# S7CAS-PLEIADES-CARTE-MERE_P07_FPGA_4-5.net
KiCad netlist of a schematic drawn in Altium Designer
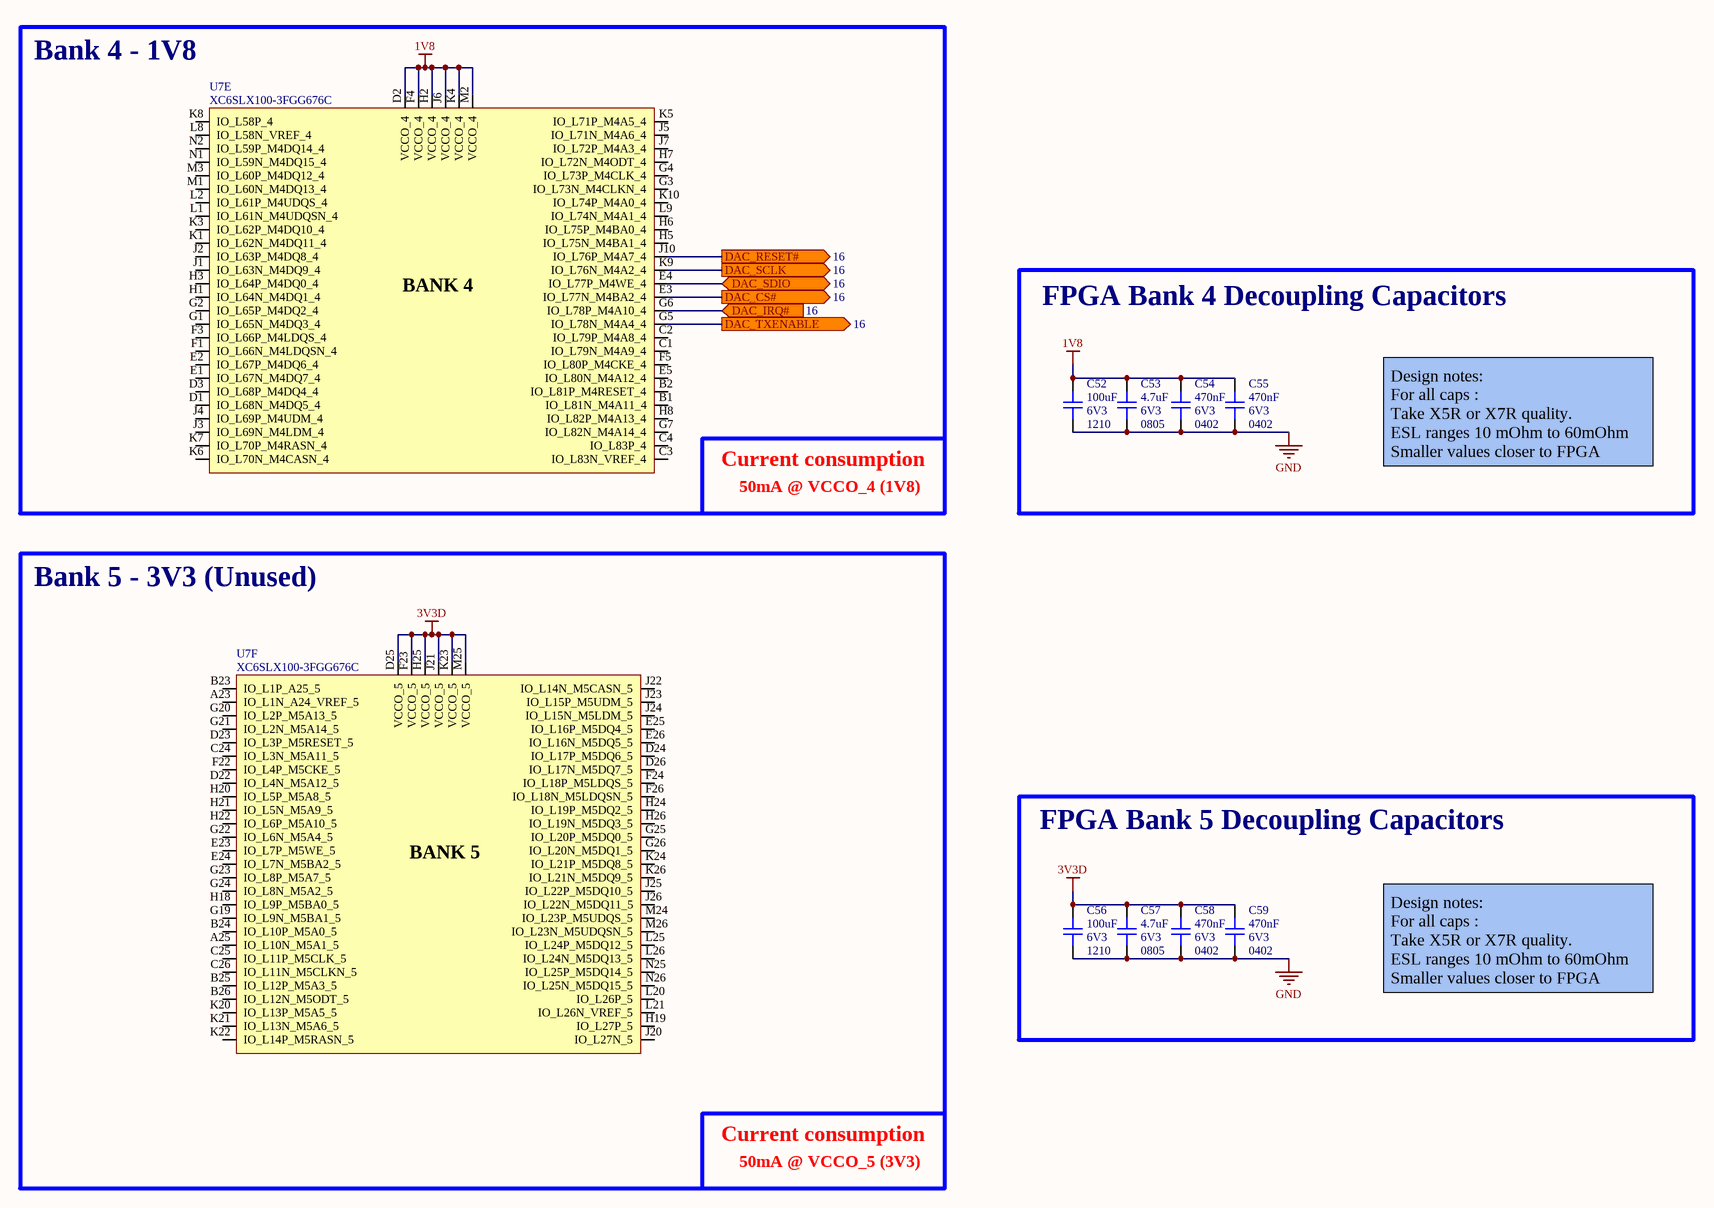
[diagram p0: S7CAS-PLEIADES-CARTE-MERE_P07_FPGA_4-5.SchDoc]

(export (version "E")
  (design (tool "Eeschema 10.0.6"))
  (components
    (comp (ref "C52")
      (value "100uF")
      (footprint "CAP_1210")
      (description "CAP - 1210")
      (fields
        (field (name "VOLTAGE") "6V3")
        (field (name "PACKAGE") "1210")
        (field (name "CREATEDBY") "Jonathan Bouchard")
      )
      (libsource (lib "S7CAS_LIB2021") (part "CAP - 1210"))
    )
    (comp (ref "C53")
      (value "4.7uF")
      (footprint "CAP_0805")
      (description "CAP - 0805")
      (fields
        (field (name "VOLTAGE") "6V3")
        (field (name "PACKAGE") "0805")
        (field (name "CREATEDBY") "Jonathan Bouchard")
      )
      (libsource (lib "S7CAS_LIB2021") (part "CAP - 0805"))
    )
    (comp (ref "C54")
      (value "470nF")
      (footprint "CAP_0402")
      (description "CAP - 0402")
      (fields
        (field (name "VOLTAGE") "6V3")
        (field (name "PACKAGE") "0402")
        (field (name "CREATEDBY") "Jonathan Bouchard")
      )
      (libsource (lib "S7CAS_LIB2021") (part "CAP - 0402"))
    )
    (comp (ref "C55")
      (value "470nF")
      (footprint "CAP_0402")
      (description "CAP - 0402")
      (fields
        (field (name "VOLTAGE") "6V3")
        (field (name "PACKAGE") "0402")
        (field (name "CREATEDBY") "Jonathan Bouchard")
      )
      (libsource (lib "S7CAS_LIB2021") (part "CAP - 0402"))
    )
    (comp (ref "C56")
      (value "100uF")
      (footprint "CAP_1210")
      (description "CAP - 1210")
      (fields
        (field (name "VOLTAGE") "6V3")
        (field (name "PACKAGE") "1210")
        (field (name "CREATEDBY") "Jonathan Bouchard")
      )
      (libsource (lib "S7CAS_LIB2021") (part "CAP - 1210"))
    )
    (comp (ref "C57")
      (value "4.7uF")
      (footprint "CAP_0805")
      (description "CAP - 0805")
      (fields
        (field (name "VOLTAGE") "6V3")
        (field (name "PACKAGE") "0805")
        (field (name "CREATEDBY") "Jonathan Bouchard")
      )
      (libsource (lib "S7CAS_LIB2021") (part "CAP - 0805"))
    )
    (comp (ref "C58")
      (value "470nF")
      (footprint "CAP_0402")
      (description "CAP - 0402")
      (fields
        (field (name "VOLTAGE") "6V3")
        (field (name "PACKAGE") "0402")
        (field (name "CREATEDBY") "Jonathan Bouchard")
      )
      (libsource (lib "S7CAS_LIB2021") (part "CAP - 0402"))
    )
    (comp (ref "C59")
      (value "470nF")
      (footprint "CAP_0402")
      (description "CAP - 0402")
      (fields
        (field (name "VOLTAGE") "6V3")
        (field (name "PACKAGE") "0402")
        (field (name "CREATEDBY") "Jonathan Bouchard")
      )
      (libsource (lib "S7CAS_LIB2021") (part "CAP - 0402"))
    )
    (comp (ref "U7")
      (value "XC6SLX100-3FGG676C")
      (footprint "FPGA_XILINX_FGG676")
      (description "FPGA - XILINX SPARTAN 6 480 I/O - BGA-676")
      (fields
        (field (name "VOLTAGE") "1.14 V ~ 1.26 V")
        (field (name "MFG") "Xilinx")
        (field (name "CREATEDBY") "Jonathan Bouchard")
      )
      (libsource (lib "S7CAS_LIB2021") (part "FPGA_XC6SLX100-3FGG676C"))
    )
  )
  (nets
    (net (code "1") (name "/DAC_CS#") (class "Default")
      (node (ref "U7") (pin "E3") (pinfunction "IO_L77N_M4BA2_4_E3") (pintype "passive"))
    )
    (net (code "2") (name "/DAC_IRQ#") (class "Default")
      (node (ref "U7") (pin "G6") (pinfunction "IO_L78P_M4A10_4_G6") (pintype "passive"))
    )
    (net (code "3") (name "/DAC_RESET#") (class "Default")
      (node (ref "U7") (pin "J10") (pinfunction "IO_L76P_M4A7_4_J10") (pintype "passive"))
    )
    (net (code "4") (name "/DAC_SCLK") (class "Default")
      (node (ref "U7") (pin "K9") (pinfunction "IO_L76N_M4A2_4_K9") (pintype "passive"))
    )
    (net (code "5") (name "/DAC_SDIO") (class "Default")
      (node (ref "U7") (pin "E4") (pinfunction "IO_L77P_M4WE_4_E4") (pintype "passive"))
    )
    (net (code "6") (name "/DAC_TXENABLE") (class "Default")
      (node (ref "U7") (pin "G5") (pinfunction "IO_L78N_M4A4_4_G5") (pintype "passive"))
    )
    (net (code "7") (name "1V8") (class "Default")
      (node (ref "C52") (pin "2") (pinfunction "2_2") (pintype "passive"))
      (node (ref "C53") (pin "2") (pinfunction "2_2") (pintype "passive"))
      (node (ref "C54") (pin "2") (pinfunction "2_2") (pintype "passive"))
      (node (ref "C55") (pin "2") (pinfunction "2_2") (pintype "passive"))
      (node (ref "U7") (pin "D2") (pinfunction "VCCO_4_D2") (pintype "passive"))
      (node (ref "U7") (pin "F4") (pinfunction "VCCO_4_F4") (pintype "passive"))
      (node (ref "U7") (pin "H2") (pinfunction "VCCO_4_H2") (pintype "passive"))
      (node (ref "U7") (pin "J6") (pinfunction "VCCO_4_J6") (pintype "passive"))
      (node (ref "U7") (pin "K4") (pinfunction "VCCO_4_K4") (pintype "passive"))
      (node (ref "U7") (pin "M2") (pinfunction "VCCO_4_M2") (pintype "passive"))
    )
    (net (code "8") (name "3V3D") (class "Default")
      (node (ref "C56") (pin "2") (pinfunction "2_2") (pintype "passive"))
      (node (ref "C57") (pin "2") (pinfunction "2_2") (pintype "passive"))
      (node (ref "C58") (pin "2") (pinfunction "2_2") (pintype "passive"))
      (node (ref "C59") (pin "2") (pinfunction "2_2") (pintype "passive"))
      (node (ref "U7") (pin "D25") (pinfunction "VCCO_5_D25") (pintype "passive"))
      (node (ref "U7") (pin "F23") (pinfunction "VCCO_5_F23") (pintype "passive"))
      (node (ref "U7") (pin "H25") (pinfunction "VCCO_5_H25") (pintype "passive"))
      (node (ref "U7") (pin "J21") (pinfunction "VCCO_5_J21") (pintype "passive"))
      (node (ref "U7") (pin "K23") (pinfunction "VCCO_5_K23") (pintype "passive"))
      (node (ref "U7") (pin "M25") (pinfunction "VCCO_5_M25") (pintype "passive"))
    )
    (net (code "9") (name "GND") (class "Default")
      (node (ref "C52") (pin "1") (pinfunction "1_1") (pintype "passive"))
      (node (ref "C53") (pin "1") (pinfunction "1_1") (pintype "passive"))
      (node (ref "C54") (pin "1") (pinfunction "1_1") (pintype "passive"))
      (node (ref "C55") (pin "1") (pinfunction "1_1") (pintype "passive"))
      (node (ref "C56") (pin "1") (pinfunction "1_1") (pintype "passive"))
      (node (ref "C57") (pin "1") (pinfunction "1_1") (pintype "passive"))
      (node (ref "C58") (pin "1") (pinfunction "1_1") (pintype "passive"))
      (node (ref "C59") (pin "1") (pinfunction "1_1") (pintype "passive"))
    )
    (net (code "10") (name "unconnected-(U7E-IO_L58N_VREF_4-PadL8)") (class "Default")
      (node (ref "U7") (pin "L8") (pinfunction "IO_L58N_VREF_4_L8") (pintype "passive"))
    )
    (net (code "11") (name "unconnected-(U7E-IO_L58P_4-PadK8)") (class "Default")
      (node (ref "U7") (pin "K8") (pinfunction "IO_L58P_4_K8") (pintype "passive"))
    )
    (net (code "12") (name "unconnected-(U7E-IO_L59N_M4DQ15_4-PadN1)") (class "Default")
      (node (ref "U7") (pin "N1") (pinfunction "IO_L59N_M4DQ15_4_N1") (pintype "passive"))
    )
    (net (code "13") (name "unconnected-(U7E-IO_L59P_M4DQ14_4-PadN2)") (class "Default")
      (node (ref "U7") (pin "N2") (pinfunction "IO_L59P_M4DQ14_4_N2") (pintype "passive"))
    )
    (net (code "14") (name "unconnected-(U7E-IO_L60N_M4DQ13_4-PadM1)") (class "Default")
      (node (ref "U7") (pin "M1") (pinfunction "IO_L60N_M4DQ13_4_M1") (pintype "passive"))
    )
    (net (code "15") (name "unconnected-(U7E-IO_L60P_M4DQ12_4-PadM3)") (class "Default")
      (node (ref "U7") (pin "M3") (pinfunction "IO_L60P_M4DQ12_4_M3") (pintype "passive"))
    )
    (net (code "16") (name "unconnected-(U7E-IO_L61N_M4UDQSN_4-PadL1)") (class "Default")
      (node (ref "U7") (pin "L1") (pinfunction "IO_L61N_M4UDQSN_4_L1") (pintype "passive"))
    )
    (net (code "17") (name "unconnected-(U7E-IO_L61P_M4UDQS_4-PadL2)") (class "Default")
      (node (ref "U7") (pin "L2") (pinfunction "IO_L61P_M4UDQS_4_L2") (pintype "passive"))
    )
    (net (code "18") (name "unconnected-(U7E-IO_L62N_M4DQ11_4-PadK1)") (class "Default")
      (node (ref "U7") (pin "K1") (pinfunction "IO_L62N_M4DQ11_4_K1") (pintype "passive"))
    )
    (net (code "19") (name "unconnected-(U7E-IO_L62P_M4DQ10_4-PadK3)") (class "Default")
      (node (ref "U7") (pin "K3") (pinfunction "IO_L62P_M4DQ10_4_K3") (pintype "passive"))
    )
    (net (code "20") (name "unconnected-(U7E-IO_L63N_M4DQ9_4-PadJ1)") (class "Default")
      (node (ref "U7") (pin "J1") (pinfunction "IO_L63N_M4DQ9_4_J1") (pintype "passive"))
    )
    (net (code "21") (name "unconnected-(U7E-IO_L63P_M4DQ8_4-PadJ2)") (class "Default")
      (node (ref "U7") (pin "J2") (pinfunction "IO_L63P_M4DQ8_4_J2") (pintype "passive"))
    )
    (net (code "22") (name "unconnected-(U7E-IO_L64N_M4DQ1_4-PadH1)") (class "Default")
      (node (ref "U7") (pin "H1") (pinfunction "IO_L64N_M4DQ1_4_H1") (pintype "passive"))
    )
    (net (code "23") (name "unconnected-(U7E-IO_L64P_M4DQ0_4-PadH3)") (class "Default")
      (node (ref "U7") (pin "H3") (pinfunction "IO_L64P_M4DQ0_4_H3") (pintype "passive"))
    )
    (net (code "24") (name "unconnected-(U7E-IO_L65N_M4DQ3_4-PadG1)") (class "Default")
      (node (ref "U7") (pin "G1") (pinfunction "IO_L65N_M4DQ3_4_G1") (pintype "passive"))
    )
    (net (code "25") (name "unconnected-(U7E-IO_L65P_M4DQ2_4-PadG2)") (class "Default")
      (node (ref "U7") (pin "G2") (pinfunction "IO_L65P_M4DQ2_4_G2") (pintype "passive"))
    )
    (net (code "26") (name "unconnected-(U7E-IO_L66N_M4LDQSN_4-PadF1)") (class "Default")
      (node (ref "U7") (pin "F1") (pinfunction "IO_L66N_M4LDQSN_4_F1") (pintype "passive"))
    )
    (net (code "27") (name "unconnected-(U7E-IO_L66P_M4LDQS_4-PadF3)") (class "Default")
      (node (ref "U7") (pin "F3") (pinfunction "IO_L66P_M4LDQS_4_F3") (pintype "passive"))
    )
    (net (code "28") (name "unconnected-(U7E-IO_L67N_M4DQ7_4-PadE1)") (class "Default")
      (node (ref "U7") (pin "E1") (pinfunction "IO_L67N_M4DQ7_4_E1") (pintype "passive"))
    )
    (net (code "29") (name "unconnected-(U7E-IO_L67P_M4DQ6_4-PadE2)") (class "Default")
      (node (ref "U7") (pin "E2") (pinfunction "IO_L67P_M4DQ6_4_E2") (pintype "passive"))
    )
    (net (code "30") (name "unconnected-(U7E-IO_L68N_M4DQ5_4-PadD1)") (class "Default")
      (node (ref "U7") (pin "D1") (pinfunction "IO_L68N_M4DQ5_4_D1") (pintype "passive"))
    )
    (net (code "31") (name "unconnected-(U7E-IO_L68P_M4DQ4_4-PadD3)") (class "Default")
      (node (ref "U7") (pin "D3") (pinfunction "IO_L68P_M4DQ4_4_D3") (pintype "passive"))
    )
    (net (code "32") (name "unconnected-(U7E-IO_L69N_M4LDM_4-PadJ3)") (class "Default")
      (node (ref "U7") (pin "J3") (pinfunction "IO_L69N_M4LDM_4_J3") (pintype "passive"))
    )
    (net (code "33") (name "unconnected-(U7E-IO_L69P_M4UDM_4-PadJ4)") (class "Default")
      (node (ref "U7") (pin "J4") (pinfunction "IO_L69P_M4UDM_4_J4") (pintype "passive"))
    )
    (net (code "34") (name "unconnected-(U7E-IO_L70N_M4CASN_4-PadK6)") (class "Default")
      (node (ref "U7") (pin "K6") (pinfunction "IO_L70N_M4CASN_4_K6") (pintype "passive"))
    )
    (net (code "35") (name "unconnected-(U7E-IO_L70P_M4RASN_4-PadK7)") (class "Default")
      (node (ref "U7") (pin "K7") (pinfunction "IO_L70P_M4RASN_4_K7") (pintype "passive"))
    )
    (net (code "36") (name "unconnected-(U7E-IO_L71N_M4A6_4-PadJ5)") (class "Default")
      (node (ref "U7") (pin "J5") (pinfunction "IO_L71N_M4A6_4_J5") (pintype "passive"))
    )
    (net (code "37") (name "unconnected-(U7E-IO_L71P_M4A5_4-PadK5)") (class "Default")
      (node (ref "U7") (pin "K5") (pinfunction "IO_L71P_M4A5_4_K5") (pintype "passive"))
    )
    (net (code "38") (name "unconnected-(U7E-IO_L72N_M4ODT_4-PadH7)") (class "Default")
      (node (ref "U7") (pin "H7") (pinfunction "IO_L72N_M4ODT_4_H7") (pintype "passive"))
    )
    (net (code "39") (name "unconnected-(U7E-IO_L72P_M4A3_4-PadJ7)") (class "Default")
      (node (ref "U7") (pin "J7") (pinfunction "IO_L72P_M4A3_4_J7") (pintype "passive"))
    )
    (net (code "40") (name "unconnected-(U7E-IO_L73N_M4CLKN_4-PadG3)") (class "Default")
      (node (ref "U7") (pin "G3") (pinfunction "IO_L73N_M4CLKN_4_G3") (pintype "passive"))
    )
    (net (code "41") (name "unconnected-(U7E-IO_L73P_M4CLK_4-PadG4)") (class "Default")
      (node (ref "U7") (pin "G4") (pinfunction "IO_L73P_M4CLK_4_G4") (pintype "passive"))
    )
    (net (code "42") (name "unconnected-(U7E-IO_L74N_M4A1_4-PadL9)") (class "Default")
      (node (ref "U7") (pin "L9") (pinfunction "IO_L74N_M4A1_4_L9") (pintype "passive"))
    )
    (net (code "43") (name "unconnected-(U7E-IO_L74P_M4A0_4-PadK10)") (class "Default")
      (node (ref "U7") (pin "K10") (pinfunction "IO_L74P_M4A0_4_K10") (pintype "passive"))
    )
    (net (code "44") (name "unconnected-(U7E-IO_L75N_M4BA1_4-PadH5)") (class "Default")
      (node (ref "U7") (pin "H5") (pinfunction "IO_L75N_M4BA1_4_H5") (pintype "passive"))
    )
    (net (code "45") (name "unconnected-(U7E-IO_L75P_M4BA0_4-PadH6)") (class "Default")
      (node (ref "U7") (pin "H6") (pinfunction "IO_L75P_M4BA0_4_H6") (pintype "passive"))
    )
    (net (code "46") (name "unconnected-(U7E-IO_L79N_M4A9_4-PadC1)") (class "Default")
      (node (ref "U7") (pin "C1") (pinfunction "IO_L79N_M4A9_4_C1") (pintype "passive"))
    )
    (net (code "47") (name "unconnected-(U7E-IO_L79P_M4A8_4-PadC2)") (class "Default")
      (node (ref "U7") (pin "C2") (pinfunction "IO_L79P_M4A8_4_C2") (pintype "passive"))
    )
    (net (code "48") (name "unconnected-(U7E-IO_L80N_M4A12_4-PadE5)") (class "Default")
      (node (ref "U7") (pin "E5") (pinfunction "IO_L80N_M4A12_4_E5") (pintype "passive"))
    )
    (net (code "49") (name "unconnected-(U7E-IO_L80P_M4CKE_4-PadF5)") (class "Default")
      (node (ref "U7") (pin "F5") (pinfunction "IO_L80P_M4CKE_4_F5") (pintype "passive"))
    )
    (net (code "50") (name "unconnected-(U7E-IO_L81N_M4A11_4-PadB1)") (class "Default")
      (node (ref "U7") (pin "B1") (pinfunction "IO_L81N_M4A11_4_B1") (pintype "passive"))
    )
    (net (code "51") (name "unconnected-(U7E-IO_L81P_M4RESET_4-PadB2)") (class "Default")
      (node (ref "U7") (pin "B2") (pinfunction "IO_L81P_M4RESET_4_B2") (pintype "passive"))
    )
    (net (code "52") (name "unconnected-(U7E-IO_L82N_M4A14_4-PadG7)") (class "Default")
      (node (ref "U7") (pin "G7") (pinfunction "IO_L82N_M4A14_4_G7") (pintype "passive"))
    )
    (net (code "53") (name "unconnected-(U7E-IO_L82P_M4A13_4-PadH8)") (class "Default")
      (node (ref "U7") (pin "H8") (pinfunction "IO_L82P_M4A13_4_H8") (pintype "passive"))
    )
    (net (code "54") (name "unconnected-(U7E-IO_L83N_VREF_4-PadC3)") (class "Default")
      (node (ref "U7") (pin "C3") (pinfunction "IO_L83N_VREF_4_C3") (pintype "passive"))
    )
    (net (code "55") (name "unconnected-(U7E-IO_L83P_4-PadC4)") (class "Default")
      (node (ref "U7") (pin "C4") (pinfunction "IO_L83P_4_C4") (pintype "passive"))
    )
    (net (code "56") (name "unconnected-(U7F-IO_L1N_A24_VREF_5-PadA23)") (class "Default")
      (node (ref "U7") (pin "A23") (pinfunction "IO_L1N_A24_VREF_5_A23") (pintype "passive"))
    )
    (net (code "57") (name "unconnected-(U7F-IO_L1P_A25_5-PadB23)") (class "Default")
      (node (ref "U7") (pin "B23") (pinfunction "IO_L1P_A25_5_B23") (pintype "passive"))
    )
    (net (code "58") (name "unconnected-(U7F-IO_L2N_M5A14_5-PadG21)") (class "Default")
      (node (ref "U7") (pin "G21") (pinfunction "IO_L2N_M5A14_5_G21") (pintype "passive"))
    )
    (net (code "59") (name "unconnected-(U7F-IO_L2P_M5A13_5-PadG20)") (class "Default")
      (node (ref "U7") (pin "G20") (pinfunction "IO_L2P_M5A13_5_G20") (pintype "passive"))
    )
    (net (code "60") (name "unconnected-(U7F-IO_L3N_M5A11_5-PadC24)") (class "Default")
      (node (ref "U7") (pin "C24") (pinfunction "IO_L3N_M5A11_5_C24") (pintype "passive"))
    )
    (net (code "61") (name "unconnected-(U7F-IO_L3P_M5RESET_5-PadD23)") (class "Default")
      (node (ref "U7") (pin "D23") (pinfunction "IO_L3P_M5RESET_5_D23") (pintype "passive"))
    )
    (net (code "62") (name "unconnected-(U7F-IO_L4N_M5A12_5-PadD22)") (class "Default")
      (node (ref "U7") (pin "D22") (pinfunction "IO_L4N_M5A12_5_D22") (pintype "passive"))
    )
    (net (code "63") (name "unconnected-(U7F-IO_L4P_M5CKE_5-PadF22)") (class "Default")
      (node (ref "U7") (pin "F22") (pinfunction "IO_L4P_M5CKE_5_F22") (pintype "passive"))
    )
    (net (code "64") (name "unconnected-(U7F-IO_L5N_M5A9_5-PadH21)") (class "Default")
      (node (ref "U7") (pin "H21") (pinfunction "IO_L5N_M5A9_5_H21") (pintype "passive"))
    )
    (net (code "65") (name "unconnected-(U7F-IO_L5P_M5A8_5-PadH20)") (class "Default")
      (node (ref "U7") (pin "H20") (pinfunction "IO_L5P_M5A8_5_H20") (pintype "passive"))
    )
    (net (code "66") (name "unconnected-(U7F-IO_L6N_M5A4_5-PadG22)") (class "Default")
      (node (ref "U7") (pin "G22") (pinfunction "IO_L6N_M5A4_5_G22") (pintype "passive"))
    )
    (net (code "67") (name "unconnected-(U7F-IO_L6P_M5A10_5-PadH22)") (class "Default")
      (node (ref "U7") (pin "H22") (pinfunction "IO_L6P_M5A10_5_H22") (pintype "passive"))
    )
    (net (code "68") (name "unconnected-(U7F-IO_L7N_M5BA2_5-PadE24)") (class "Default")
      (node (ref "U7") (pin "E24") (pinfunction "IO_L7N_M5BA2_5_E24") (pintype "passive"))
    )
    (net (code "69") (name "unconnected-(U7F-IO_L7P_M5WE_5-PadE23)") (class "Default")
      (node (ref "U7") (pin "E23") (pinfunction "IO_L7P_M5WE_5_E23") (pintype "passive"))
    )
    (net (code "70") (name "unconnected-(U7F-IO_L8N_M5A2_5-PadG24)") (class "Default")
      (node (ref "U7") (pin "G24") (pinfunction "IO_L8N_M5A2_5_G24") (pintype "passive"))
    )
    (net (code "71") (name "unconnected-(U7F-IO_L8P_M5A7_5-PadG23)") (class "Default")
      (node (ref "U7") (pin "G23") (pinfunction "IO_L8P_M5A7_5_G23") (pintype "passive"))
    )
    (net (code "72") (name "unconnected-(U7F-IO_L9N_M5BA1_5-PadG19)") (class "Default")
      (node (ref "U7") (pin "G19") (pinfunction "IO_L9N_M5BA1_5_G19") (pintype "passive"))
    )
    (net (code "73") (name "unconnected-(U7F-IO_L9P_M5BA0_5-PadH18)") (class "Default")
      (node (ref "U7") (pin "H18") (pinfunction "IO_L9P_M5BA0_5_H18") (pintype "passive"))
    )
    (net (code "74") (name "unconnected-(U7F-IO_L10N_M5A1_5-PadA25)") (class "Default")
      (node (ref "U7") (pin "A25") (pinfunction "IO_L10N_M5A1_5_A25") (pintype "passive"))
    )
    (net (code "75") (name "unconnected-(U7F-IO_L10P_M5A0_5-PadB24)") (class "Default")
      (node (ref "U7") (pin "B24") (pinfunction "IO_L10P_M5A0_5_B24") (pintype "passive"))
    )
    (net (code "76") (name "unconnected-(U7F-IO_L11N_M5CLKN_5-PadC26)") (class "Default")
      (node (ref "U7") (pin "C26") (pinfunction "IO_L11N_M5CLKN_5_C26") (pintype "passive"))
    )
    (net (code "77") (name "unconnected-(U7F-IO_L11P_M5CLK_5-PadC25)") (class "Default")
      (node (ref "U7") (pin "C25") (pinfunction "IO_L11P_M5CLK_5_C25") (pintype "passive"))
    )
    (net (code "78") (name "unconnected-(U7F-IO_L12N_M5ODT_5-PadB26)") (class "Default")
      (node (ref "U7") (pin "B26") (pinfunction "IO_L12N_M5ODT_5_B26") (pintype "passive"))
    )
    (net (code "79") (name "unconnected-(U7F-IO_L12P_M5A3_5-PadB25)") (class "Default")
      (node (ref "U7") (pin "B25") (pinfunction "IO_L12P_M5A3_5_B25") (pintype "passive"))
    )
    (net (code "80") (name "unconnected-(U7F-IO_L13N_M5A6_5-PadK21)") (class "Default")
      (node (ref "U7") (pin "K21") (pinfunction "IO_L13N_M5A6_5_K21") (pintype "passive"))
    )
    (net (code "81") (name "unconnected-(U7F-IO_L13P_M5A5_5-PadK20)") (class "Default")
      (node (ref "U7") (pin "K20") (pinfunction "IO_L13P_M5A5_5_K20") (pintype "passive"))
    )
    (net (code "82") (name "unconnected-(U7F-IO_L14N_M5CASN_5-PadJ22)") (class "Default")
      (node (ref "U7") (pin "J22") (pinfunction "IO_L14N_M5CASN_5_J22") (pintype "passive"))
    )
    (net (code "83") (name "unconnected-(U7F-IO_L14P_M5RASN_5-PadK22)") (class "Default")
      (node (ref "U7") (pin "K22") (pinfunction "IO_L14P_M5RASN_5_K22") (pintype "passive"))
    )
    (net (code "84") (name "unconnected-(U7F-IO_L15N_M5LDM_5-PadJ24)") (class "Default")
      (node (ref "U7") (pin "J24") (pinfunction "IO_L15N_M5LDM_5_J24") (pintype "passive"))
    )
    (net (code "85") (name "unconnected-(U7F-IO_L15P_M5UDM_5-PadJ23)") (class "Default")
      (node (ref "U7") (pin "J23") (pinfunction "IO_L15P_M5UDM_5_J23") (pintype "passive"))
    )
    (net (code "86") (name "unconnected-(U7F-IO_L16N_M5DQ5_5-PadE26)") (class "Default")
      (node (ref "U7") (pin "E26") (pinfunction "IO_L16N_M5DQ5_5_E26") (pintype "passive"))
    )
    (net (code "87") (name "unconnected-(U7F-IO_L16P_M5DQ4_5-PadE25)") (class "Default")
      (node (ref "U7") (pin "E25") (pinfunction "IO_L16P_M5DQ4_5_E25") (pintype "passive"))
    )
    (net (code "88") (name "unconnected-(U7F-IO_L17N_M5DQ7_5-PadD26)") (class "Default")
      (node (ref "U7") (pin "D26") (pinfunction "IO_L17N_M5DQ7_5_D26") (pintype "passive"))
    )
    (net (code "89") (name "unconnected-(U7F-IO_L17P_M5DQ6_5-PadD24)") (class "Default")
      (node (ref "U7") (pin "D24") (pinfunction "IO_L17P_M5DQ6_5_D24") (pintype "passive"))
    )
    (net (code "90") (name "unconnected-(U7F-IO_L18N_M5LDQSN_5-PadF26)") (class "Default")
      (node (ref "U7") (pin "F26") (pinfunction "IO_L18N_M5LDQSN_5_F26") (pintype "passive"))
    )
    (net (code "91") (name "unconnected-(U7F-IO_L18P_M5LDQS_5-PadF24)") (class "Default")
      (node (ref "U7") (pin "F24") (pinfunction "IO_L18P_M5LDQS_5_F24") (pintype "passive"))
    )
    (net (code "92") (name "unconnected-(U7F-IO_L19N_M5DQ3_5-PadH26)") (class "Default")
      (node (ref "U7") (pin "H26") (pinfunction "IO_L19N_M5DQ3_5_H26") (pintype "passive"))
    )
    (net (code "93") (name "unconnected-(U7F-IO_L19P_M5DQ2_5-PadH24)") (class "Default")
      (node (ref "U7") (pin "H24") (pinfunction "IO_L19P_M5DQ2_5_H24") (pintype "passive"))
    )
    (net (code "94") (name "unconnected-(U7F-IO_L20N_M5DQ1_5-PadG26)") (class "Default")
      (node (ref "U7") (pin "G26") (pinfunction "IO_L20N_M5DQ1_5_G26") (pintype "passive"))
    )
    (net (code "95") (name "unconnected-(U7F-IO_L20P_M5DQ0_5-PadG25)") (class "Default")
      (node (ref "U7") (pin "G25") (pinfunction "IO_L20P_M5DQ0_5_G25") (pintype "passive"))
    )
    (net (code "96") (name "unconnected-(U7F-IO_L21N_M5DQ9_5-PadK26)") (class "Default")
      (node (ref "U7") (pin "K26") (pinfunction "IO_L21N_M5DQ9_5_K26") (pintype "passive"))
    )
    (net (code "97") (name "unconnected-(U7F-IO_L21P_M5DQ8_5-PadK24)") (class "Default")
      (node (ref "U7") (pin "K24") (pinfunction "IO_L21P_M5DQ8_5_K24") (pintype "passive"))
    )
    (net (code "98") (name "unconnected-(U7F-IO_L22N_M5DQ11_5-PadJ26)") (class "Default")
      (node (ref "U7") (pin "J26") (pinfunction "IO_L22N_M5DQ11_5_J26") (pintype "passive"))
    )
    (net (code "99") (name "unconnected-(U7F-IO_L22P_M5DQ10_5-PadJ25)") (class "Default")
      (node (ref "U7") (pin "J25") (pinfunction "IO_L22P_M5DQ10_5_J25") (pintype "passive"))
    )
    (net (code "100") (name "unconnected-(U7F-IO_L23N_M5UDQSN_5-PadM26)") (class "Default")
      (node (ref "U7") (pin "M26") (pinfunction "IO_L23N_M5UDQSN_5_M26") (pintype "passive"))
    )
    (net (code "101") (name "unconnected-(U7F-IO_L23P_M5UDQS_5-PadM24)") (class "Default")
      (node (ref "U7") (pin "M24") (pinfunction "IO_L23P_M5UDQS_5_M24") (pintype "passive"))
    )
    (net (code "102") (name "unconnected-(U7F-IO_L24N_M5DQ13_5-PadL26)") (class "Default")
      (node (ref "U7") (pin "L26") (pinfunction "IO_L24N_M5DQ13_5_L26") (pintype "passive"))
    )
    (net (code "103") (name "unconnected-(U7F-IO_L24P_M5DQ12_5-PadL25)") (class "Default")
      (node (ref "U7") (pin "L25") (pinfunction "IO_L24P_M5DQ12_5_L25") (pintype "passive"))
    )
    (net (code "104") (name "unconnected-(U7F-IO_L25N_M5DQ15_5-PadN26)") (class "Default")
      (node (ref "U7") (pin "N26") (pinfunction "IO_L25N_M5DQ15_5_N26") (pintype "passive"))
    )
    (net (code "105") (name "unconnected-(U7F-IO_L25P_M5DQ14_5-PadN25)") (class "Default")
      (node (ref "U7") (pin "N25") (pinfunction "IO_L25P_M5DQ14_5_N25") (pintype "passive"))
    )
    (net (code "106") (name "unconnected-(U7F-IO_L26N_VREF_5-PadL21)") (class "Default")
      (node (ref "U7") (pin "L21") (pinfunction "IO_L26N_VREF_5_L21") (pintype "passive"))
    )
    (net (code "107") (name "unconnected-(U7F-IO_L26P_5-PadL20)") (class "Default")
      (node (ref "U7") (pin "L20") (pinfunction "IO_L26P_5_L20") (pintype "passive"))
    )
    (net (code "108") (name "unconnected-(U7F-IO_L27N_5-PadJ20)") (class "Default")
      (node (ref "U7") (pin "J20") (pinfunction "IO_L27N_5_J20") (pintype "passive"))
    )
    (net (code "109") (name "unconnected-(U7F-IO_L27P_5-PadH19)") (class "Default")
      (node (ref "U7") (pin "H19") (pinfunction "IO_L27P_5_H19") (pintype "passive"))
    )
  )
)
